# ST_LINK_V3E.net
KiCad netlist of a schematic drawn in Altium Designer
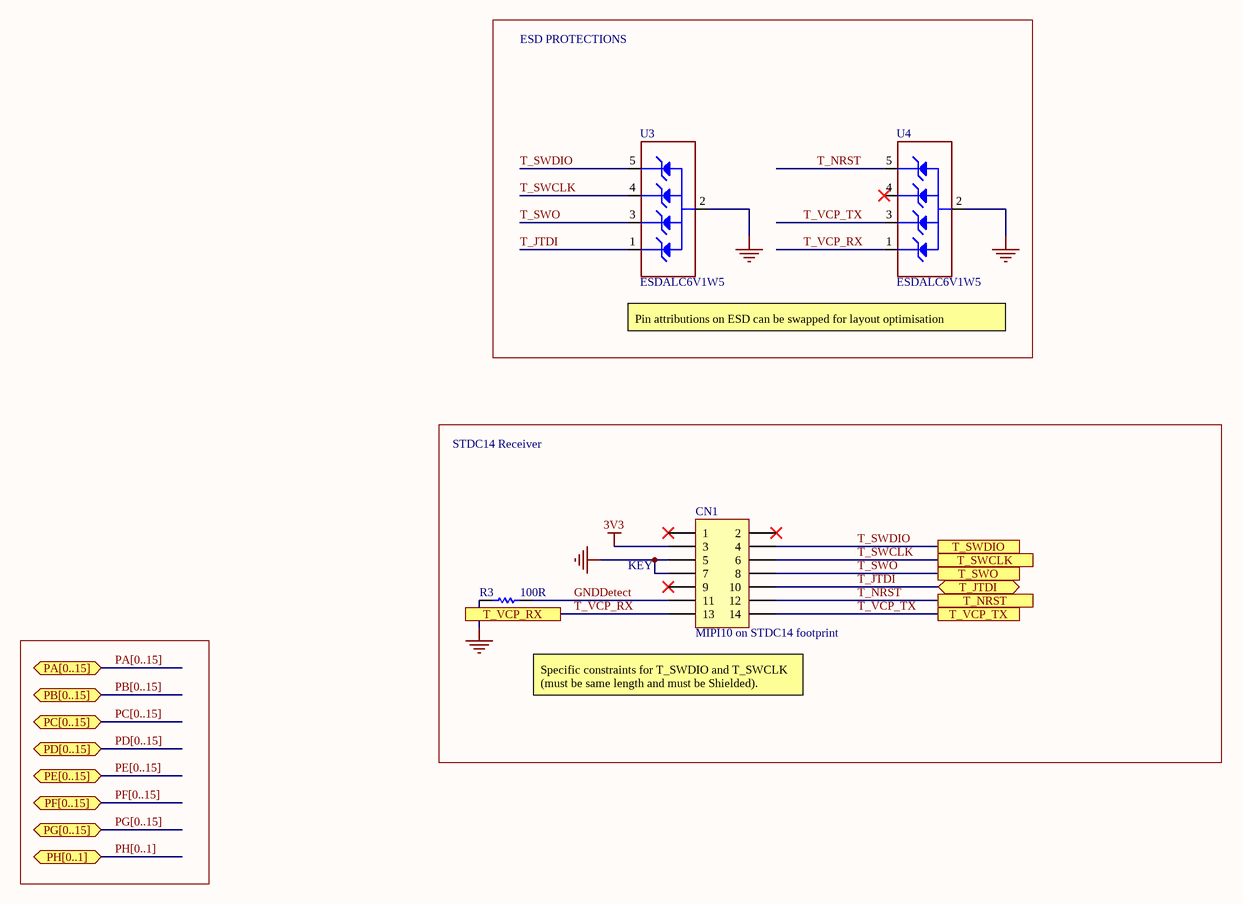
[diagram p0: ST_LINK_V3E.SchDoc]

(export (version "E")
  (design (tool "Eeschema 10.0.6"))
  (components
    (comp (ref "CN1")
      (value "MIPI10 on STDC14 footprint")
      (footprint "CON_STDC14_Receiver_MEDIUM_WITH_MIPI10_3D")
      (fields
        (field (name "INTERNAL_PART_NUMBER") "MCD-01226")
        (field (name "MANUFACTURER_PART_NUMBER") "FTSH-105-01-L-DV-K")
        (field (name "MANUFACTURER") "SAMTEC")
        (field (name "PROVIDED_BY") "SUBCO")
      )
      (libsource (lib "MCD_PARTS_database") (part "Header 7x2"))
    )
    (comp (ref "R3")
      (value "100R")
      (footprint "R0402")
      (description "Resistor,100R,0402,1%,1/16W")
      (fields
        (field (name "INTERNAL_PART_NUMBER") "MCD-00119")
        (field (name "MANUFACTURER_PART_NUMBER") "RC0402FR-07100RL")
        (field (name "PROVIDED_BY") "SUBCO")
      )
      (libsource (lib "MCD_PARTS_database") (part "Resistor"))
    )
    (comp (ref "U3")
      (value "ESDALC6V1W5")
      (footprint "ESD_SOT323-5L")
      (description "Dual Transil array for ESD protection")
      (fields
        (field (name "INTERNAL_PART_NUMBER") "MCD-00136")
        (field (name "MANUFACTURER") "STMICROELECTRONICS")
        (field (name "PROVIDED_BY") "SUBCO with ST control")
      )
      (libsource (lib "MCD_PARTS_database") (part "ESDALC6V1W5"))
    )
    (comp (ref "U4")
      (value "ESDALC6V1W5")
      (footprint "ESD_SOT323-5L")
      (description "Dual Transil array for ESD protection")
      (fields
        (field (name "INTERNAL_PART_NUMBER") "MCD-00136")
        (field (name "MANUFACTURER") "STMICROELECTRONICS")
        (field (name "PROVIDED_BY") "SUBCO with ST control")
      )
      (libsource (lib "MCD_PARTS_database") (part "ESDALC6V1W5"))
    )
  )
  (nets
    (net (code "115") (name "/GNDDetect") (class "Default")
      (node (ref "CN1") (pin "11") (pinfunction "11_11") (pintype "passive"))
      (node (ref "R3") (pin "2") (pinfunction "2_2") (pintype "passive"))
    )
    (net (code "124") (name "/T_JTDI") (class "Default")
      (node (ref "CN1") (pin "10") (pinfunction "10_10") (pintype "passive"))
      (node (ref "U3") (pin "1") (pinfunction "IO1_1") (pintype "passive"))
    )
    (net (code "125") (name "/T_NRST") (class "Default")
      (node (ref "CN1") (pin "12") (pinfunction "12_12") (pintype "passive"))
      (node (ref "U4") (pin "5") (pinfunction "IO4_5") (pintype "passive"))
    )
    (net (code "126") (name "/T_SWCLK") (class "Default")
      (node (ref "CN1") (pin "6") (pinfunction "6_6") (pintype "passive"))
      (node (ref "U3") (pin "4") (pinfunction "IO3_4") (pintype "passive"))
    )
    (net (code "127") (name "/T_SWDIO") (class "Default")
      (node (ref "CN1") (pin "4") (pinfunction "4_4") (pintype "passive"))
      (node (ref "U3") (pin "5") (pinfunction "IO4_5") (pintype "passive"))
    )
    (net (code "128") (name "/T_SWO") (class "Default")
      (node (ref "CN1") (pin "8") (pinfunction "8_8") (pintype "passive"))
      (node (ref "U3") (pin "3") (pinfunction "IO2_3") (pintype "passive"))
    )
    (net (code "129") (name "/T_VCP_RX") (class "Default")
      (node (ref "CN1") (pin "13") (pinfunction "13_13") (pintype "passive"))
      (node (ref "U4") (pin "1") (pinfunction "IO1_1") (pintype "passive"))
    )
    (net (code "130") (name "/T_VCP_TX") (class "Default")
      (node (ref "CN1") (pin "14") (pinfunction "14_14") (pintype "passive"))
      (node (ref "U4") (pin "3") (pinfunction "IO2_3") (pintype "passive"))
    )
    (net (code "131") (name "3V3") (class "Default")
      (node (ref "CN1") (pin "3") (pinfunction "3_3") (pintype "passive"))
    )
    (net (code "132") (name "GND") (class "Default")
      (node (ref "CN1") (pin "5") (pinfunction "5_5") (pintype "passive"))
      (node (ref "CN1") (pin "7") (pinfunction "7_7") (pintype "passive"))
      (node (ref "R3") (pin "1") (pinfunction "1_1") (pintype "passive"))
      (node (ref "U3") (pin "2") (pinfunction "GND_2") (pintype "passive"))
      (node (ref "U4") (pin "2") (pinfunction "GND_2") (pintype "passive"))
    )
    (net (code "133") (name "unconnected-(CN1-Pad1)") (class "Default")
      (node (ref "CN1") (pin "1") (pinfunction "1_1") (pintype "passive+no_connect"))
    )
    (net (code "134") (name "unconnected-(CN1-Pad2)") (class "Default")
      (node (ref "CN1") (pin "2") (pinfunction "2_2") (pintype "passive+no_connect"))
    )
    (net (code "135") (name "unconnected-(CN1-Pad9)") (class "Default")
      (node (ref "CN1") (pin "9") (pinfunction "9_9") (pintype "passive+no_connect"))
    )
    (net (code "136") (name "unconnected-(U4-IO3-Pad4)") (class "Default")
      (node (ref "U4") (pin "4") (pinfunction "IO3_4") (pintype "passive+no_connect"))
    )
  )
)
